# power.net
KiCad netlist of a schematic drawn in Altium Designer
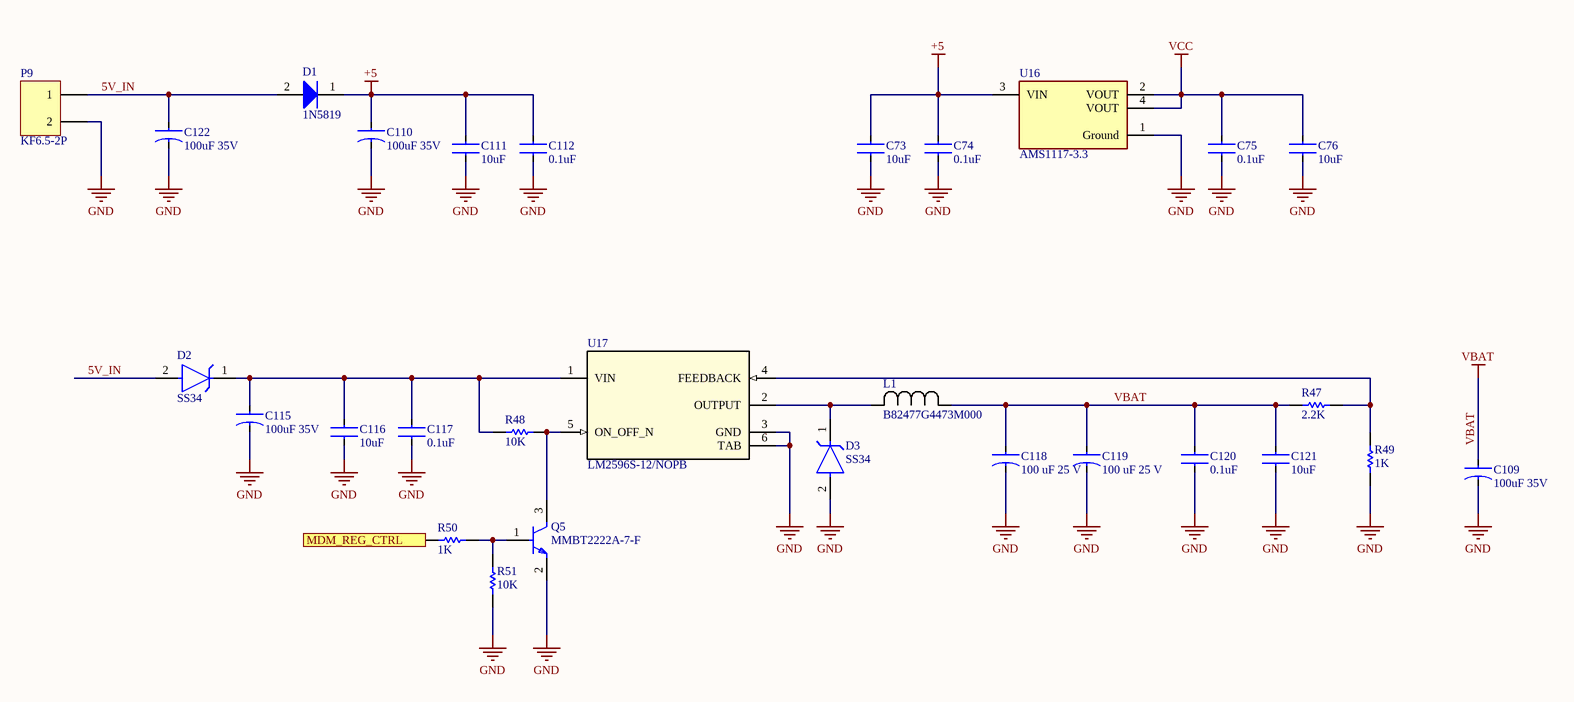
[diagram p0: power.SchDoc]

(export (version "E")
  (design (tool "Eeschema 10.0.6"))
  (components
    (comp (ref "C73")
      (value "10uF")
      (footprint "C0402")
      (description "Cap Ceramic 10uF 16V X7R 10% Pad SMD 1206 125°C T/R")
      (fields
        (field (name "MANUFACTURER") "Samsung")
        (field (name "MANUFACTURER PART NUMBER") "CL31B106KOHNNNE")
      )
      (libsource (lib "afra") (part "CL31B106KOHNNNE"))
    )
    (comp (ref "C74")
      (value "0.1uF")
      (footprint "C0402")
      (description "Ceramic capacitor SMD-1206 100nF /50V X7R# K +-10%, Samsung, RoHS")
      (fields
        (field (name "MANUFACTURER") "Samsung")
        (field (name "MANUFACTURER PART NUMBER") "CL31B104KBCNNNC")
      )
      (libsource (lib "afra") (part "CL31B104KBCNNNC"))
    )
    (comp (ref "C75")
      (value "0.1uF")
      (footprint "C0402")
      (description "Ceramic capacitor SMD-1206 100nF /50V X7R# K +-10%, Samsung, RoHS")
      (fields
        (field (name "MANUFACTURER") "Samsung")
        (field (name "MANUFACTURER PART NUMBER") "CL31B104KBCNNNC")
      )
      (libsource (lib "afra") (part "CL31B104KBCNNNC"))
    )
    (comp (ref "C76")
      (value "10uF")
      (footprint "C0402")
      (description "Cap Ceramic 10uF 16V X7R 10% Pad SMD 1206 125°C T/R")
      (fields
        (field (name "MANUFACTURER") "Samsung")
        (field (name "MANUFACTURER PART NUMBER") "CL31B106KOHNNNE")
      )
      (libsource (lib "afra") (part "CL31B106KOHNNNE"))
    )
    (comp (ref "C109")
      (value "100uF 35V")
      (footprint "CAP_J-V_10X10P5_RUB")
      (description "Aluminum Electrolytic Capacitors Radial, Can - 1000 Hrs @ 105°C")
      (fields
        (field (name "MANUFACTURER") "Panasonic")
        (field (name "MANUFACTURER PART NUMBER") "EEU-HD1V101")
      )
      (libsource (lib "afra") (part "100 uF 35 V Electrolytic Capacitors Radial"))
    )
    (comp (ref "C110")
      (value "100uF 35V")
      (footprint "CAP_J-V_10X10P5_RUB")
      (description "Aluminum Electrolytic Capacitors Radial, Can - 1000 Hrs @ 105°C")
      (fields
        (field (name "MANUFACTURER") "Panasonic")
        (field (name "MANUFACTURER PART NUMBER") "EEU-HD1V101")
      )
      (libsource (lib "afra") (part "100 uF 35 V Electrolytic Capacitors Radial"))
    )
    (comp (ref "C111")
      (value "10uF")
      (footprint "C0402")
      (description "Cap Ceramic 10uF 16V X7R 10% Pad SMD 1206 125°C T/R")
      (fields
        (field (name "MANUFACTURER") "Samsung")
        (field (name "MANUFACTURER PART NUMBER") "CL31B106KOHNNNE")
      )
      (libsource (lib "afra") (part "CL31B106KOHNNNE"))
    )
    (comp (ref "C112")
      (value "0.1uF")
      (footprint "C0402")
      (description "Ceramic capacitor SMD-1206 100nF /50V X7R# K +-10%, Samsung, RoHS")
      (fields
        (field (name "MANUFACTURER") "Samsung")
        (field (name "MANUFACTURER PART NUMBER") "CL31B104KBCNNNC")
      )
      (libsource (lib "afra") (part "CL31B104KBCNNNC"))
    )
    (comp (ref "C115")
      (value "100uF 35V")
      (footprint "CAP_J-V_10X10P5_RUB")
      (description "Aluminum Electrolytic Capacitors Radial, Can - 1000 Hrs @ 105°C")
      (fields
        (field (name "MANUFACTURER") "Panasonic")
        (field (name "MANUFACTURER PART NUMBER") "EEU-HD1V101")
      )
      (libsource (lib "afra") (part "100 uF 35 V Electrolytic Capacitors Radial"))
    )
    (comp (ref "C116")
      (value "10uF")
      (footprint "C0402")
      (description "Cap Ceramic 10uF 16V X7R 10% Pad SMD 1206 125°C T/R")
      (fields
        (field (name "MANUFACTURER") "Samsung")
        (field (name "MANUFACTURER PART NUMBER") "CL31B106KOHNNNE")
      )
      (libsource (lib "afra") (part "CL31B106KOHNNNE"))
    )
    (comp (ref "C117")
      (value "0.1uF")
      (footprint "C0402")
      (description "Ceramic capacitor SMD-1206 100nF /50V X7R# K +-10%, Samsung, RoHS")
      (fields
        (field (name "MANUFACTURER") "Samsung")
        (field (name "MANUFACTURER PART NUMBER") "CL31B104KBCNNNC")
      )
      (libsource (lib "afra") (part "CL31B104KBCNNNC"))
    )
    (comp (ref "C118")
      (value "100 uF 25 V")
      (footprint "CAP_J-V_10X10P5_RUB")
      (description "RZ Series Radial 25 V 100 uF Ø 6.3 x 11 mm 105 °C Electrolytic Capacitor")
      (fields
        (field (name "MANUFACTURER") "Samwha")
        (field (name "MANUFACTURER PART NUMBER") "RZ1E107M6L011BB280")
      )
      (libsource (lib "afra") (part "100 uF 25 V Electrolytic Capacitor"))
    )
    (comp (ref "C119")
      (value "100 uF 25 V")
      (footprint "CAP_J-V_10X10P5_RUB")
      (description "RZ Series Radial 25 V 100 uF Ø 6.3 x 11 mm 105 °C Electrolytic Capacitor")
      (fields
        (field (name "MANUFACTURER") "Samwha")
        (field (name "MANUFACTURER PART NUMBER") "RZ1E107M6L011BB280")
      )
      (libsource (lib "afra") (part "100 uF 25 V Electrolytic Capacitor"))
    )
    (comp (ref "C120")
      (value "0.1uF")
      (footprint "C0402")
      (description "Ceramic capacitor SMD-1206 100nF /50V X7R# K +-10%, Samsung, RoHS")
      (fields
        (field (name "MANUFACTURER") "Samsung")
        (field (name "MANUFACTURER PART NUMBER") "CL31B104KBCNNNC")
      )
      (libsource (lib "afra") (part "CL31B104KBCNNNC"))
    )
    (comp (ref "C121")
      (value "10uF")
      (footprint "C0402")
      (description "Cap Ceramic 10uF 16V X7R 10% Pad SMD 1206 125°C T/R")
      (fields
        (field (name "MANUFACTURER") "Samsung")
        (field (name "MANUFACTURER PART NUMBER") "CL31B106KOHNNNE")
      )
      (libsource (lib "afra") (part "CL31B106KOHNNNE"))
    )
    (comp (ref "C122")
      (value "100uF 35V")
      (footprint "CAP_J-V_10X10P5_RUB")
      (description "Aluminum Electrolytic Capacitors Radial, Can - 1000 Hrs @ 105°C")
      (fields
        (field (name "MANUFACTURER") "Panasonic")
        (field (name "MANUFACTURER PART NUMBER") "EEU-HD1V101")
      )
      (libsource (lib "afra") (part "100 uF 35 V Electrolytic Capacitors Radial"))
    )
    (comp (ref "D1")
      (value "1N5819")
      (footprint "SMA (DO-214AC)")
      (description "Rectifier, 2-Pin Axial_Lead, Pb-Free, Tape and Reel")
      (fields (field (name "MANUFACTURER") "On Semiconductor") (field (name "PARTNUMBER") "1N5819RLG"))
      (libsource (lib "afra") (part "1N5819RLG"))
    )
    (comp (ref "D2")
      (value "SS34")
      (footprint "SMA (DO-214AC)")
      (description "DIODE SCHOTTKY 40V 3A SMC")
      (libsource (lib "afra") (part "SS34"))
    )
    (comp (ref "D3")
      (value "SS34")
      (footprint "SMA (DO-214AC)")
      (description "DIODE SCHOTTKY 40V 3A SMC")
      (libsource (lib "afra") (part "SS34"))
    )
    (comp (ref "L1")
      (value "B82477G4473M000")
      (footprint "IND_EPCOS_B82477G4_EPC")
      (description "No Description Available")
      (fields (field (name "COPYRIGHT") "Copyright (C) 2022 Ultra Librarian. All rights reserved."))
      (libsource (lib "afra") (part "B82477G4473M000"))
    )
    (comp (ref "P9")
      (value "KF6.5-2P")
      (footprint "KF6.5 2P 11mm")
      (libsource (lib "afra") (part "KF6.5-2P Barrier Terminal Block"))
    )
    (comp (ref "Q5")
      (value "MMBT2222A-7-F")
      (footprint "SOT-23-3L_AOS")
      (description "NPN Ic=600mA Vceo=40V hfe=100~300 fT=300MHz P=310mW SOT-23")
      (fields (field (name "MANUFACTURER") "Diodes") (field (name "VOLTAGE") "40V"))
      (libsource (lib "afra") (part "MMBT2222A-7-F"))
    )
    (comp (ref "R47")
      (value "2.2K")
      (footprint "R0402")
      (description "Res Thick Film 1206 2.2K Ohm 1% 0.25W(1/4W) ±100ppm/C Pad SMD T/R")
      (fields
        (field (name "MANUFACTURER") "Yageo")
        (field (name "MANUFACTURER PART NUMBER") "RC1206FR-072K2L")
      )
      (libsource (lib "afra") (part "RC1206FR-072K2L"))
    )
    (comp (ref "R48")
      (value "10K")
      (footprint "R0402")
      (description "Res Thick Film 1206 10K Ohm 1% 0.25W(1/4W) ±100ppm/C Pad SMD T/R")
      (fields
        (field (name "MANUFACTURER") "Yageo")
        (field (name "MANUFACTURER PART NUMBER") "RC1206FR-0710KL")
      )
      (libsource (lib "afra") (part "RC1206FR-0710KL"))
    )
    (comp (ref "R49")
      (value "1K")
      (footprint "R0402")
      (description "In a Pack of 5000, 1K 1206 Thick Film SMD Resistor ±1% 0.25W - RC1206FR-071KL")
      (fields
        (field (name "MANUFACTURER") "Yageo")
        (field (name "MANUFACTURER PART NUMBER") "RC1206FR-071KL")
      )
      (libsource (lib "afra") (part "RC1206FR-071KL"))
    )
    (comp (ref "R50")
      (value "1K")
      (footprint "R0402")
      (description "In a Pack of 5000, 1K 1206 Thick Film SMD Resistor ±1% 0.25W - RC1206FR-071KL")
      (fields
        (field (name "MANUFACTURER") "Yageo")
        (field (name "MANUFACTURER PART NUMBER") "RC1206FR-071KL")
      )
      (libsource (lib "afra") (part "RC1206FR-071KL"))
    )
    (comp (ref "R51")
      (value "10K")
      (footprint "R0402")
      (description "Res Thick Film 1206 10K Ohm 1% 0.25W(1/4W) ±100ppm/C Pad SMD T/R")
      (fields
        (field (name "MANUFACTURER") "Yageo")
        (field (name "MANUFACTURER PART NUMBER") "RC1206FR-0710KL")
      )
      (libsource (lib "afra") (part "RC1206FR-0710KL"))
    )
    (comp (ref "U16")
      (value "AMS1117-3.3")
      (footprint "Advanced_Monolithic_Systems_AMS1117_IPC_A")
      (description "Fixed 15V 3.3V 1.3V @ 800mA SOT-223 Dropout Regulators(LDO) RoHS")
      (libsource (lib "afra") (part "AMS1117-3.3"))
    )
    (comp (ref "U17")
      (value "LM2596S-12/NOPB")
      (footprint "KTT0005B")
      (description "No Description Available")
      (fields
        (field (name "PARTNUMBER") "LM2596SX-ADJ/NOPB")
        (field (name "ALTERNATE_PARTNUMBER") "LM2596S-ADJ/NOPB")
        (field (name "COPYRIGHT") "Copyright (C) 2022 Ultra Librarian. All rights reserved.")
      )
      (libsource (lib "afra") (part "LM2596S-12/NOPB"))
    )
  )
  (nets
    (net (code "1") (name "+5") (class "Default")
      (node (ref "C110") (pin "1") (pinfunction "1_1") (pintype "passive"))
      (node (ref "C111") (pin "1") (pinfunction "1_1") (pintype "passive"))
      (node (ref "C112") (pin "1") (pinfunction "1_1") (pintype "passive"))
      (node (ref "C73") (pin "1") (pinfunction "1_1") (pintype "passive"))
      (node (ref "C74") (pin "1") (pinfunction "1_1") (pintype "passive"))
      (node (ref "D1") (pin "1") (pinfunction "K_1") (pintype "passive"))
      (node (ref "U16") (pin "3") (pinfunction "VIN_3") (pintype "power_in"))
    )
    (net (code "2") (name "/5V_IN") (class "Default")
      (node (ref "C122") (pin "1") (pinfunction "1_1") (pintype "passive"))
      (node (ref "D1") (pin "2") (pinfunction "A_2") (pintype "passive"))
      (node (ref "D2") (pin "2") (pinfunction "A_2") (pintype "passive"))
      (node (ref "P9") (pin "1") (pinfunction "1_1") (pintype "passive"))
    )
    (net (code "3") (name "/MDM_REG_CTRL") (class "Default")
      (node (ref "R50") (pin "1") (pinfunction "1_1") (pintype "passive"))
    )
    (net (code "4") (name "GND") (class "Default")
      (node (ref "C109") (pin "2") (pinfunction "2_2") (pintype "passive"))
      (node (ref "C110") (pin "2") (pinfunction "2_2") (pintype "passive"))
      (node (ref "C111") (pin "2") (pinfunction "2_2") (pintype "passive"))
      (node (ref "C112") (pin "2") (pinfunction "2_2") (pintype "passive"))
      (node (ref "C115") (pin "2") (pinfunction "2_2") (pintype "passive"))
      (node (ref "C116") (pin "2") (pinfunction "2_2") (pintype "passive"))
      (node (ref "C117") (pin "2") (pinfunction "2_2") (pintype "passive"))
      (node (ref "C118") (pin "2") (pinfunction "2_2") (pintype "passive"))
      (node (ref "C119") (pin "2") (pinfunction "2_2") (pintype "passive"))
      (node (ref "C120") (pin "2") (pinfunction "2_2") (pintype "passive"))
      (node (ref "C121") (pin "2") (pinfunction "2_2") (pintype "passive"))
      (node (ref "C122") (pin "2") (pinfunction "2_2") (pintype "passive"))
      (node (ref "C73") (pin "2") (pinfunction "2_2") (pintype "passive"))
      (node (ref "C74") (pin "2") (pinfunction "2_2") (pintype "passive"))
      (node (ref "C75") (pin "2") (pinfunction "2_2") (pintype "passive"))
      (node (ref "C76") (pin "2") (pinfunction "2_2") (pintype "passive"))
      (node (ref "D3") (pin "2") (pinfunction "A_2") (pintype "passive"))
      (node (ref "P9") (pin "2") (pinfunction "2_2") (pintype "passive"))
      (node (ref "Q5") (pin "2") (pinfunction "E_2") (pintype "passive"))
      (node (ref "R49") (pin "1") (pinfunction "1_1") (pintype "passive"))
      (node (ref "R51") (pin "1") (pinfunction "1_1") (pintype "passive"))
      (node (ref "U16") (pin "1") (pinfunction "Ground_1") (pintype "power_in"))
      (node (ref "U17") (pin "3") (pinfunction "GND_3") (pintype "power_in"))
      (node (ref "U17") (pin "6") (pinfunction "TAB_6") (pintype "power_in"))
    )
    (net (code "5") (name "Net-(D2-C)") (class "Default")
      (node (ref "C115") (pin "1") (pinfunction "1_1") (pintype "passive"))
      (node (ref "C116") (pin "1") (pinfunction "1_1") (pintype "passive"))
      (node (ref "C117") (pin "1") (pinfunction "1_1") (pintype "passive"))
      (node (ref "D2") (pin "1") (pinfunction "C_1") (pintype "passive"))
      (node (ref "R48") (pin "2") (pinfunction "2_2") (pintype "passive"))
      (node (ref "U17") (pin "1") (pinfunction "VIN_1") (pintype "power_in"))
    )
    (net (code "6") (name "Net-(D3-C)") (class "Default")
      (node (ref "D3") (pin "1") (pinfunction "C_1") (pintype "passive"))
      (node (ref "L1") (pin "2") (pinfunction "2_2") (pintype "passive"))
      (node (ref "U17") (pin "2") (pinfunction "OUTPUT_2") (pintype "power_in"))
    )
    (net (code "7") (name "Net-(Q5-B)") (class "Default")
      (node (ref "Q5") (pin "1") (pinfunction "B_1") (pintype "passive"))
      (node (ref "R50") (pin "2") (pinfunction "2_2") (pintype "passive"))
      (node (ref "R51") (pin "2") (pinfunction "2_2") (pintype "passive"))
    )
    (net (code "8") (name "Net-(Q5-C)") (class "Default")
      (node (ref "Q5") (pin "3") (pinfunction "C_3") (pintype "passive"))
      (node (ref "R48") (pin "1") (pinfunction "1_1") (pintype "passive"))
      (node (ref "U17") (pin "5") (pinfunction "ON_OFF_N_5") (pintype "input"))
    )
    (net (code "9") (name "Net-(U17-FEEDBACK)") (class "Default")
      (node (ref "R47") (pin "1") (pinfunction "1_1") (pintype "passive"))
      (node (ref "R49") (pin "2") (pinfunction "2_2") (pintype "passive"))
      (node (ref "U17") (pin "4") (pinfunction "FEEDBACK_4") (pintype "input"))
    )
    (net (code "10") (name "VBAT") (class "Default")
      (node (ref "C109") (pin "1") (pinfunction "1_1") (pintype "passive"))
      (node (ref "C118") (pin "1") (pinfunction "1_1") (pintype "passive"))
      (node (ref "C119") (pin "1") (pinfunction "1_1") (pintype "passive"))
      (node (ref "C120") (pin "1") (pinfunction "1_1") (pintype "passive"))
      (node (ref "C121") (pin "1") (pinfunction "1_1") (pintype "passive"))
      (node (ref "L1") (pin "1") (pinfunction "1_1") (pintype "passive"))
      (node (ref "R47") (pin "2") (pinfunction "2_2") (pintype "passive"))
    )
    (net (code "11") (name "VCC") (class "Default")
      (node (ref "C75") (pin "1") (pinfunction "1_1") (pintype "passive"))
      (node (ref "C76") (pin "1") (pinfunction "1_1") (pintype "passive"))
      (node (ref "U16") (pin "2") (pinfunction "VOUT_2") (pintype "passive"))
      (node (ref "U16") (pin "4") (pinfunction "VOUT_4") (pintype "passive"))
    )
  )
)
